# Teensy.net
KiCad netlist of a schematic drawn in Altium Designer
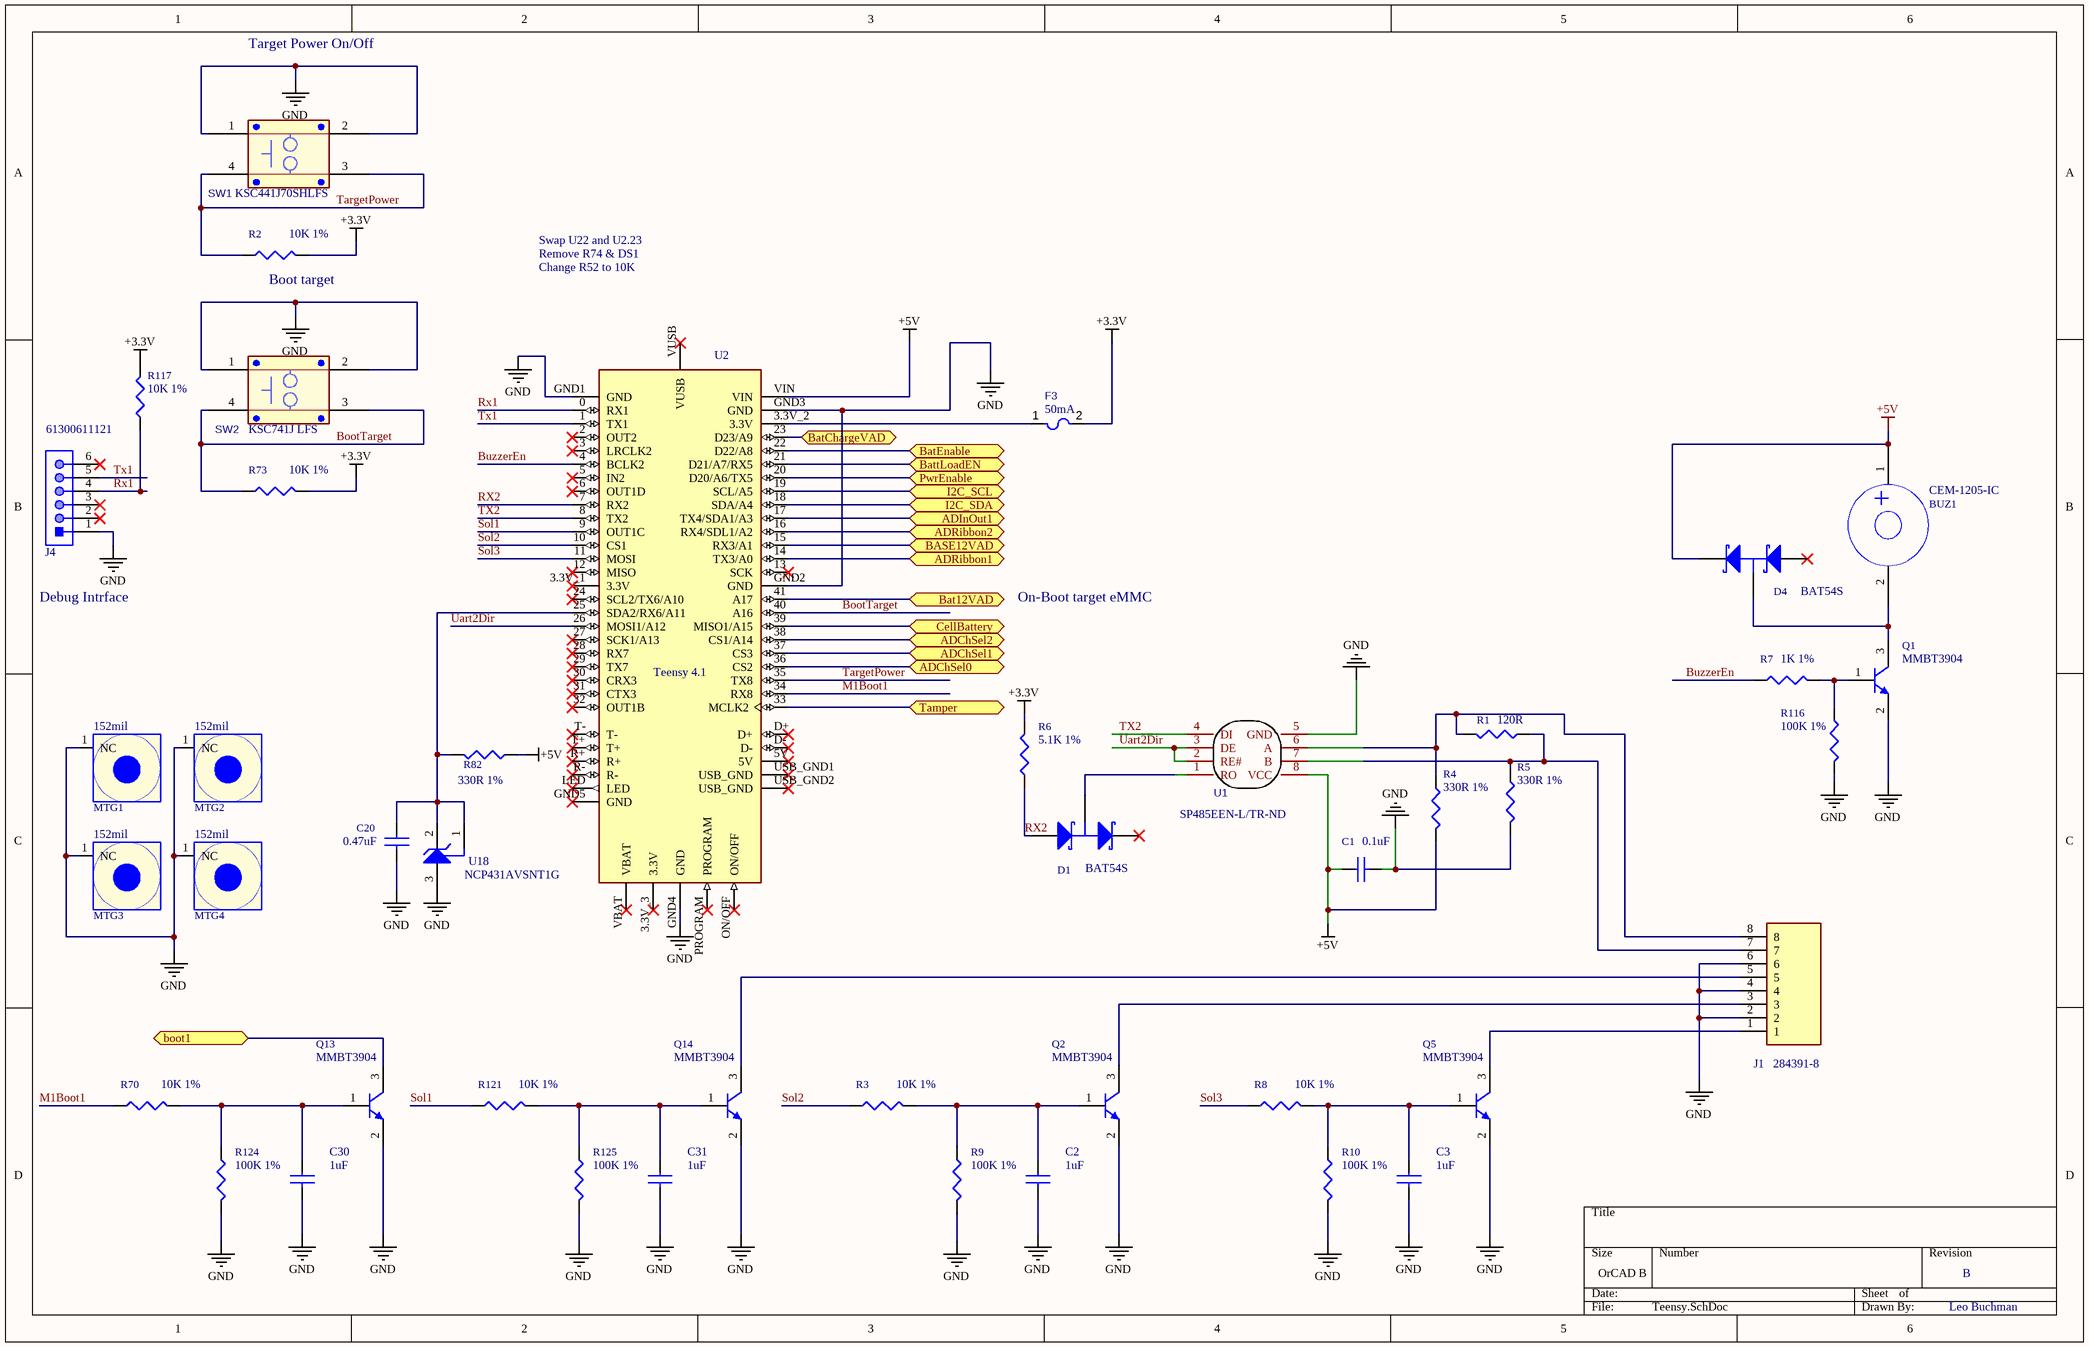
[diagram p0: Teensy.SchDoc]

(export (version "E")
  (design (tool "Eeschema 10.0.6"))
  (components
    (comp (ref "BUZ1")
      (value "CEM-1205-IC")
      (footprint "BUZZ-MB5120C")
      (description "12 mm, 5 Vdc, 92 dB, Through Hole, Driving Circuit, Magnetic Audio Indicator Buzzer")
      (fields (field (name "ADI PART NUMBER") "3716-0001") (field (name "VOLTAGE") "5V"))
      (libsource (lib "Leo-Home-SQL-Lib") (part "S2-BZ-0001"))
    )
    (comp (ref "C1")
      (value "0.1uF")
      (footprint "C0402")
      (description "Cap Ceramic 0.1uF 50V X7R 10% Pad SMD 0402 125C Automotive T/R")
      (fields
        (field (name "MANUFACTURER") "Murata")
        (field (name "MANUFACTURER PART NUMBER") "GRT155R71H104KE01D")
      )
      (libsource (lib "Leo-Home-SQL-Lib") (part "CAPNP"))
    )
    (comp (ref "C2")
      (value "1uF")
      (footprint "C0402")
      (description "CAP CER 1UF 10V Y5V 0402")
      (fields
        (field (name "MANUFACTURER") "KEMET")
        (field (name "MANUFACTURER PART NUMBER") "C0402C105Z8VAC7867")
      )
      (libsource (lib "Leo-Home-SQL-Lib") (part "CAPNP"))
    )
    (comp (ref "C3")
      (value "1uF")
      (footprint "C0402")
      (description "CAP CER 1UF 10V Y5V 0402")
      (fields
        (field (name "MANUFACTURER") "KEMET")
        (field (name "MANUFACTURER PART NUMBER") "C0402C105Z8VAC7867")
      )
      (libsource (lib "Leo-Home-SQL-Lib") (part "CAPNP"))
    )
    (comp (ref "C20")
      (value "0.47uF")
      (footprint "C0402")
      (description "CAP CER 0.47UF 16V Y5V 0402")
      (fields
        (field (name "MANUFACTURER") "Yageo")
        (field (name "MANUFACTURER PART NUMBER") "CC0402ZRY5V7BB474")
      )
      (libsource (lib "Leo-Home-SQL-Lib") (part "CAPNP"))
    )
    (comp (ref "C30")
      (value "1uF")
      (footprint "C0402")
      (description "CAP CER 1UF 10V Y5V 0402")
      (fields
        (field (name "MANUFACTURER") "KEMET")
        (field (name "MANUFACTURER PART NUMBER") "C0402C105Z8VAC7867")
      )
      (libsource (lib "Leo-Home-SQL-Lib") (part "CAPNP"))
    )
    (comp (ref "C31")
      (value "1uF")
      (footprint "C0402")
      (description "CAP CER 1UF 10V Y5V 0402")
      (fields
        (field (name "MANUFACTURER") "KEMET")
        (field (name "MANUFACTURER PART NUMBER") "C0402C105Z8VAC7867")
      )
      (libsource (lib "Leo-Home-SQL-Lib") (part "CAPNP"))
    )
    (comp (ref "D1")
      (value "BAT54S")
      (footprint "sot23-3")
      (description "DIODE SCHOTTKY 30V 150MA SOT23-3")
      (fields
        (field (name "MANUFACTURER") "Sangdest Microelectronics")
        (field (name "MANUFACTURER_1") "ON Semiconductor / Fairchild")
      )
      (libsource (lib "Leo-Home-SQL-Lib") (part "BAT54S-7-F"))
    )
    (comp (ref "D4")
      (value "BAT54S")
      (footprint "sot23-3")
      (description "DIODE SCHOTTKY 30V 150MA SOT23-3")
      (fields
        (field (name "MANUFACTURER") "Sangdest Microelectronics")
        (field (name "MANUFACTURER_1") "ON Semiconductor / Fairchild")
      )
      (libsource (lib "Leo-Home-SQL-Lib") (part "BAT54S-7-F"))
    )
    (comp (ref "F3")
      (value "50mA")
      (footprint "F0603")
      (description "Ptc Reset Fuse 15V 50MA 0603")
      (fields (field (name "MANUFACTURER") "Littelfuse") (field (name "MANUFACTURER_1") "Bourns"))
      (libsource (lib "Leo-Home-SQL-Lib") (part "FusePTC"))
    )
    (comp (ref "J1")
      (value "284391-8")
      (footprint "TE_284391-8")
      (description "Conn Terminal Block F 8 POS 3.5mm Solder ST T")
      (fields (field (name "MF") "TE Connectivity") (field (name "DIGI-KEY_PART_NUMBER") "A98163-ND"))
      (libsource (lib "Leo-Home-SQL-Lib") (part "284391-8"))
    )
    (comp (ref "J4")
      (value "61300611121")
      (footprint "61300611121")
      (description "CONN HEADER 6 POS 2.54")
      (fields (field (name "MANUFACTURER") "Wurth Electronics") (field (name "LCSC PART NUMBER") "C2833331"))
      (libsource (lib "Leo-Home-SQL-Lib") (part "CMP-1502-01070-1"))
    )
    (comp (ref "MTG1")
      (value "152mil")
      (footprint "MNT-HOLE-169-350")
      (description "Plated")
      (libsource (lib "Leo-Home-SQL-Lib") (part "HoleSym-001"))
    )
    (comp (ref "MTG2")
      (value "152mil")
      (footprint "MNT-HOLE-169-350")
      (description "Plated")
      (libsource (lib "Leo-Home-SQL-Lib") (part "HoleSym-001"))
    )
    (comp (ref "MTG3")
      (value "152mil")
      (footprint "MNT-HOLE-169-350")
      (description "Plated")
      (libsource (lib "Leo-Home-SQL-Lib") (part "HoleSym-001"))
    )
    (comp (ref "MTG4")
      (value "152mil")
      (footprint "MNT-HOLE-169-350")
      (description "Plated")
      (libsource (lib "Leo-Home-SQL-Lib") (part "HoleSym-001"))
    )
    (comp (ref "Q1")
      (value "MMBT3904")
      (footprint "sot23-3")
      (description "Trans GP BJT NPN 60V 0.2A 350mW Automotive 3-Pin SOT-23 T/R")
      (fields (field (name "MANUFACTURER") "ON Semiconductor / Fairchild") (field (name "POWER") "225mW"))
      (libsource (lib "Leo-Home-SQL-Lib") (part "BJT-NPN"))
    )
    (comp (ref "Q2")
      (value "MMBT3904")
      (footprint "sot23-3")
      (description "Trans GP BJT NPN 60V 0.2A 350mW Automotive 3-Pin SOT-23 T/R")
      (fields (field (name "MANUFACTURER") "ON Semiconductor / Fairchild") (field (name "POWER") "225mW"))
      (libsource (lib "Leo-Home-SQL-Lib") (part "BJT-NPN"))
    )
    (comp (ref "Q5")
      (value "MMBT3904")
      (footprint "sot23-3")
      (description "Trans GP BJT NPN 60V 0.2A 350mW Automotive 3-Pin SOT-23 T/R")
      (fields (field (name "MANUFACTURER") "ON Semiconductor / Fairchild") (field (name "POWER") "225mW"))
      (libsource (lib "Leo-Home-SQL-Lib") (part "BJT-NPN"))
    )
    (comp (ref "Q13")
      (value "MMBT3904")
      (footprint "sot23-3")
      (description "Trans GP BJT NPN 60V 0.2A 350mW Automotive 3-Pin SOT-23 T/R")
      (fields (field (name "MANUFACTURER") "ON Semiconductor / Fairchild") (field (name "POWER") "225mW"))
      (libsource (lib "Leo-Home-SQL-Lib") (part "BJT-NPN"))
    )
    (comp (ref "Q14")
      (value "MMBT3904")
      (footprint "sot23-3")
      (description "Trans GP BJT NPN 60V 0.2A 350mW Automotive 3-Pin SOT-23 T/R")
      (fields (field (name "MANUFACTURER") "ON Semiconductor / Fairchild") (field (name "POWER") "225mW"))
      (libsource (lib "Leo-Home-SQL-Lib") (part "BJT-NPN"))
    )
    (comp (ref "R1")
      (value "120R")
      (footprint "R0402")
      (description "Res Thick Film 0402 120 Ohm 1% 0.063W(1/16W) ±100ppm/C Pad SMD Automotive T/R")
      (fields
        (field (name "MANUFACTURER") "Stackpole Electronics")
        (field (name "MANUFACTURER PART NUMBER") "RMCF0402FT120R")
      )
      (libsource (lib "Leo-Home-SQL-Lib") (part "Resistor"))
    )
    (comp (ref "R2")
      (value "10K 1%")
      (footprint "R0402")
      (description "Thick Film 0402 10K OHM 1% 1/16W 0402")
      (fields
        (field (name "MANUFACTURER") "Yageo")
        (field (name "MANUFACTURER PART NUMBER") "RC0402FR-0710KP")
      )
      (libsource (lib "Leo-Home-SQL-Lib") (part "Resistor"))
    )
    (comp (ref "R3")
      (value "10K 1%")
      (footprint "R0402")
      (description "Thick Film 0402 10K OHM 1% 1/16W 0402")
      (fields
        (field (name "MANUFACTURER") "Yageo")
        (field (name "MANUFACTURER PART NUMBER") "RC0402FR-0710KP")
      )
      (libsource (lib "Leo-Home-SQL-Lib") (part "Resistor"))
    )
    (comp (ref "R4")
      (value "330R 1%")
      (footprint "R0402")
      (description "Thick Film 0402 330 Ohm 1% 1/16W ±100ppm/°C Molded SMD Paper T/R")
      (fields
        (field (name "MANUFACTURER") "Yageo")
        (field (name "MANUFACTURER PART NUMBER") "AF0402FR-07330RL")
      )
      (libsource (lib "Leo-Home-SQL-Lib") (part "Resistor"))
    )
    (comp (ref "R5")
      (value "330R 1%")
      (footprint "R0402")
      (description "Thick Film 0402 330 Ohm 1% 1/16W ±100ppm/°C Molded SMD Paper T/R")
      (fields
        (field (name "MANUFACTURER") "Yageo")
        (field (name "MANUFACTURER PART NUMBER") "AF0402FR-07330RL")
      )
      (libsource (lib "Leo-Home-SQL-Lib") (part "Resistor"))
    )
    (comp (ref "R6")
      (value "5.1K 1%")
      (footprint "R0402")
      (description "Thick Film 0402 5.1K Ohm 1% 1/16W 0402")
      (fields
        (field (name "MANUFACTURER") "Stackpole Electronics")
        (field (name "MANUFACTURER PART NUMBER") "RMCF0402FT5K10")
      )
      (libsource (lib "Leo-Home-SQL-Lib") (part "Resistor"))
    )
    (comp (ref "R7")
      (value "1K 1%")
      (footprint "R0402")
      (description "Thick Film 0402 1K Ohm 1% 1/8W 0402")
      (fields
        (field (name "MANUFACTURER") "TE Connectivity")
        (field (name "MANUFACTURER PART NUMBER") "CRGP0402F1K0")
      )
      (libsource (lib "Leo-Home-SQL-Lib") (part "Resistor"))
    )
    (comp (ref "R8")
      (value "10K 1%")
      (footprint "R0402")
      (description "Thick Film 0402 10K OHM 1% 1/16W 0402")
      (fields
        (field (name "MANUFACTURER") "Yageo")
        (field (name "MANUFACTURER PART NUMBER") "RC0402FR-0710KP")
      )
      (libsource (lib "Leo-Home-SQL-Lib") (part "Resistor"))
    )
    (comp (ref "R9")
      (value "100K 1%")
      (footprint "R0402")
      (description "Thick Film 0402 100K OHM 1% 1/16W 0402")
      (fields
        (field (name "MANUFACTURER") "Stackpole Electronics")
        (field (name "MANUFACTURER PART NUMBER") "RMCF0402FT100K")
      )
      (libsource (lib "Leo-Home-SQL-Lib") (part "Resistor"))
    )
    (comp (ref "R10")
      (value "100K 1%")
      (footprint "R0402")
      (description "Thick Film 0402 100K OHM 1% 1/16W 0402")
      (fields
        (field (name "MANUFACTURER") "Stackpole Electronics")
        (field (name "MANUFACTURER PART NUMBER") "RMCF0402FT100K")
      )
      (libsource (lib "Leo-Home-SQL-Lib") (part "Resistor"))
    )
    (comp (ref "R70")
      (value "10K 1%")
      (footprint "R0402")
      (description "Thick Film 0402 10K OHM 1% 1/16W 0402")
      (fields
        (field (name "MANUFACTURER") "Yageo")
        (field (name "MANUFACTURER PART NUMBER") "RC0402FR-0710KP")
      )
      (libsource (lib "Leo-Home-SQL-Lib") (part "Resistor"))
    )
    (comp (ref "R73")
      (value "10K 1%")
      (footprint "R0402")
      (description "Thick Film 0402 10K OHM 1% 1/16W 0402")
      (fields
        (field (name "MANUFACTURER") "Yageo")
        (field (name "MANUFACTURER PART NUMBER") "RC0402FR-0710KP")
      )
      (libsource (lib "Leo-Home-SQL-Lib") (part "Resistor"))
    )
    (comp (ref "R82")
      (value "330R 1%")
      (footprint "R0402")
      (description "Thick Film 0402 330 Ohm 1% 1/16W ±100ppm/°C Molded SMD Paper T/R")
      (fields
        (field (name "MANUFACTURER") "Yageo")
        (field (name "MANUFACTURER PART NUMBER") "AF0402FR-07330RL")
      )
      (libsource (lib "Leo-Home-SQL-Lib") (part "Resistor"))
    )
    (comp (ref "R116")
      (value "100K 1%")
      (footprint "R0402")
      (description "Thick Film 0402 100K OHM 1% 1/16W 0402")
      (fields
        (field (name "MANUFACTURER") "Stackpole Electronics")
        (field (name "MANUFACTURER PART NUMBER") "RMCF0402FT100K")
      )
      (libsource (lib "Leo-Home-SQL-Lib") (part "Resistor"))
    )
    (comp (ref "R117")
      (value "10K 1%")
      (footprint "R0402")
      (description "Thick Film 0402 10K OHM 1% 1/16W 0402")
      (fields
        (field (name "MANUFACTURER") "Yageo")
        (field (name "MANUFACTURER PART NUMBER") "RC0402FR-0710KP")
      )
      (libsource (lib "Leo-Home-SQL-Lib") (part "Resistor"))
    )
    (comp (ref "R121")
      (value "10K 1%")
      (footprint "R0402")
      (description "Thick Film 0402 10K OHM 1% 1/16W 0402")
      (fields
        (field (name "MANUFACTURER") "Yageo")
        (field (name "MANUFACTURER PART NUMBER") "RC0402FR-0710KP")
      )
      (libsource (lib "Leo-Home-SQL-Lib") (part "Resistor"))
    )
    (comp (ref "R124")
      (value "100K 1%")
      (footprint "R0402")
      (description "Thick Film 0402 100K OHM 1% 1/16W 0402")
      (fields
        (field (name "MANUFACTURER") "Stackpole Electronics")
        (field (name "MANUFACTURER PART NUMBER") "RMCF0402FT100K")
      )
      (libsource (lib "Leo-Home-SQL-Lib") (part "Resistor"))
    )
    (comp (ref "R125")
      (value "100K 1%")
      (footprint "R0402")
      (description "Thick Film 0402 100K OHM 1% 1/16W 0402")
      (fields
        (field (name "MANUFACTURER") "Stackpole Electronics")
        (field (name "MANUFACTURER PART NUMBER") "RMCF0402FT100K")
      )
      (libsource (lib "Leo-Home-SQL-Lib") (part "Resistor"))
    )
    (comp (ref "SW1")
      (value "KSC441J70SHLFS")
      (footprint "SON4_KSC741JLFS_CNK-red")
      (description "Switch Tactile N.O. SPST Round Button J-Bend")
      (fields (field (name "LCSC PART NUMBER") "C221748") (field (name "MANUFACTURER") "ITT C&K"))
      (libsource (lib "Leo-Home-SQL-Lib") (part "SW_Tactile"))
    )
    (comp (ref "SW2")
      (value "KSC741J LFS")
      (footprint "SON4_KSC741JLFS_CNK-blue")
      (description "Switch Tactile N.O. SPST Round Button J-Bend")
      (fields (field (name "LCSC PART NUMBER") "C221766") (field (name "MANUFACTURER") "ITT C&K"))
      (libsource (lib "Leo-Home-SQL-Lib") (part "SW_Tactile"))
    )
    (comp (ref "U1")
      (value "SP485EEN-L/TR-ND")
      (footprint "NSOIC-8")
      (description "IC TXRX RS485 HALF DUPLEX 8SOIC")
      (fields
        (field (name "BOM_MANUFACTURER PART") "SP485EEN-L/TR")
        (field (name "BOM_SUPPLIER PART") "C6855")
      )
      (libsource (lib "Leo-Home-SQL-Lib") (part "SP485EEN-L/TR"))
    )
    (comp (ref "U2")
      (value "Teensy 4.1")
      (footprint "MODULE_DEV-16771 - headers")
      (description "Teensy 4.1 Development Board")
      (fields (field (name "MANUFACTURER") "SparkFun") (field (name "MANUFACTURER PART NUMBER") "DEV-16771"))
      (libsource (lib "Leo-Home-SQL-Lib") (part "DEV-16771"))
    )
    (comp (ref "U18")
      (value "NCP431AVSNT1G")
      (footprint "sot23-3")
      (description "V-Ref Adjustable 2.5V to 36V 100mA 3-Pin SOT-")
      (fields (field (name "MANUFACTURER") "ON Semiconductor") (field (name "PARTNUMBER") "TL431ACLP"))
      (libsource (lib "Leo-Home-SQL-Lib") (part "CMP-0366-00039-2"))
    )
  )
  (nets
    (net (code "1") (name "+3.3V") (class "Default")
      (node (ref "F3") (pin "2") (pinfunction "2_2") (pintype "passive"))
      (node (ref "R117") (pin "2") (pinfunction "2_2") (pintype "passive"))
      (node (ref "R2") (pin "2") (pinfunction "2_2") (pintype "passive"))
      (node (ref "R6") (pin "2") (pinfunction "2_2") (pintype "passive"))
      (node (ref "R73") (pin "2") (pinfunction "2_2") (pintype "passive"))
    )
    (net (code "2") (name "+5V") (class "Default")
      (node (ref "BUZ1") (pin "1") (pinfunction "POS_1") (pintype "power_in"))
      (node (ref "C1") (pin "1") (pinfunction "1_1") (pintype "passive"))
      (node (ref "D4") (pin "2") (pinfunction "K_2") (pintype "passive"))
      (node (ref "R4") (pin "2") (pinfunction "2_2") (pintype "passive"))
      (node (ref "R82") (pin "1") (pinfunction "1_1") (pintype "passive"))
      (node (ref "U1") (pin "8") (pinfunction "VCC_8") (pintype "passive"))
      (node (ref "U2") (pin "VIN") (pinfunction "VIN_VIN") (pintype "power_in"))
    )
    (net (code "3") (name "/ADChSel0") (class "Default")
      (node (ref "U2") (pin "36") (pinfunction "CS2_36") (pintype "bidirectional"))
    )
    (net (code "4") (name "/ADChSel1") (class "Default")
      (node (ref "U2") (pin "37") (pinfunction "CS3_37") (pintype "bidirectional"))
    )
    (net (code "5") (name "/ADChSel2") (class "Default")
      (node (ref "U2") (pin "38") (pinfunction "CS1/A14_38") (pintype "bidirectional"))
    )
    (net (code "6") (name "/ADInOut1") (class "Default")
      (node (ref "U2") (pin "17") (pinfunction "TX4/SDA1/A3_17") (pintype "bidirectional"))
    )
    (net (code "7") (name "/ADRibbon1") (class "Default")
      (node (ref "U2") (pin "14") (pinfunction "TX3/A0_14") (pintype "bidirectional"))
    )
    (net (code "8") (name "/ADRibbon2") (class "Default")
      (node (ref "U2") (pin "16") (pinfunction "RX4/SDL1/A2_16") (pintype "bidirectional"))
    )
    (net (code "9") (name "/BASE12VAD") (class "Default")
      (node (ref "U2") (pin "15") (pinfunction "RX3/A1_15") (pintype "bidirectional"))
    )
    (net (code "10") (name "/Bat12VAD") (class "Default")
      (node (ref "U2") (pin "41") (pinfunction "A17_41") (pintype "bidirectional"))
    )
    (net (code "11") (name "/BatChargeVAD") (class "Default")
      (node (ref "U2") (pin "23") (pinfunction "D23/A9_23") (pintype "bidirectional"))
    )
    (net (code "12") (name "/BatEnable") (class "Default")
      (node (ref "U2") (pin "22") (pinfunction "D22/A8_22") (pintype "bidirectional"))
    )
    (net (code "13") (name "/BattLoadEN") (class "Default")
      (node (ref "U2") (pin "21") (pinfunction "D21/A7/RX5_21") (pintype "bidirectional"))
    )
    (net (code "14") (name "/BootTarget") (class "Default")
      (node (ref "R73") (pin "1") (pinfunction "1_1") (pintype "passive"))
      (node (ref "SW2") (pin "3") (pinfunction "3_3") (pintype "passive"))
      (node (ref "SW2") (pin "4") (pinfunction "4_4") (pintype "passive"))
      (node (ref "U2") (pin "40") (pinfunction "A16_40") (pintype "bidirectional"))
    )
    (net (code "15") (name "/BuzzerEn") (class "Default")
      (node (ref "R7") (pin "1") (pinfunction "1_1") (pintype "passive"))
      (node (ref "U2") (pin "4") (pinfunction "BCLK2_4") (pintype "bidirectional"))
    )
    (net (code "16") (name "/CellBattery") (class "Default")
      (node (ref "U2") (pin "39") (pinfunction "MISO1/A15_39") (pintype "bidirectional"))
    )
    (net (code "17") (name "/I2C_SCL") (class "Default")
      (node (ref "U2") (pin "19") (pinfunction "SCL/A5_19") (pintype "bidirectional"))
    )
    (net (code "18") (name "/I2C_SDA") (class "Default")
      (node (ref "U2") (pin "18") (pinfunction "SDA/A4_18") (pintype "bidirectional"))
    )
    (net (code "19") (name "/M1Boot1") (class "Default")
      (node (ref "R70") (pin "1") (pinfunction "1_1") (pintype "passive"))
      (node (ref "U2") (pin "34") (pinfunction "RX8_34") (pintype "bidirectional"))
    )
    (net (code "20") (name "/PwrEnable") (class "Default")
      (node (ref "U2") (pin "20") (pinfunction "D20/A6/TX5_20") (pintype "bidirectional"))
    )
    (net (code "21") (name "/RX2") (class "Default")
      (node (ref "D1") (pin "1") (pinfunction "A_1") (pintype "passive"))
      (node (ref "R6") (pin "1") (pinfunction "1_1") (pintype "passive"))
      (node (ref "U2") (pin "7") (pinfunction "RX2_7") (pintype "bidirectional"))
    )
    (net (code "22") (name "/Rx1") (class "Default")
      (node (ref "J4") (pin "4") (pinfunction "4_4") (pintype "passive"))
      (node (ref "R117") (pin "1") (pinfunction "1_1") (pintype "passive"))
      (node (ref "U2") (pin "0") (pinfunction "RX1_0") (pintype "bidirectional"))
    )
    (net (code "23") (name "/Sol1") (class "Default")
      (node (ref "R121") (pin "1") (pinfunction "1_1") (pintype "passive"))
      (node (ref "U2") (pin "9") (pinfunction "OUT1C_9") (pintype "bidirectional"))
    )
    (net (code "24") (name "/Sol2") (class "Default")
      (node (ref "R3") (pin "1") (pinfunction "1_1") (pintype "passive"))
      (node (ref "U2") (pin "10") (pinfunction "CS1_10") (pintype "bidirectional"))
    )
    (net (code "25") (name "/Sol3") (class "Default")
      (node (ref "R8") (pin "1") (pinfunction "1_1") (pintype "passive"))
      (node (ref "U2") (pin "11") (pinfunction "MOSI_11") (pintype "bidirectional"))
    )
    (net (code "26") (name "/TX2") (class "Default")
      (node (ref "U1") (pin "4") (pinfunction "DI_4") (pintype "passive"))
      (node (ref "U2") (pin "8") (pinfunction "TX2_8") (pintype "bidirectional"))
    )
    (net (code "27") (name "/Tamper") (class "Default")
      (node (ref "U2") (pin "33") (pinfunction "MCLK2_33") (pintype "bidirectional"))
    )
    (net (code "28") (name "/TargetPower") (class "Default")
      (node (ref "R2") (pin "1") (pinfunction "1_1") (pintype "passive"))
      (node (ref "SW1") (pin "3") (pinfunction "3_3") (pintype "passive"))
      (node (ref "SW1") (pin "4") (pinfunction "4_4") (pintype "passive"))
      (node (ref "U2") (pin "35") (pinfunction "TX8_35") (pintype "bidirectional"))
    )
    (net (code "29") (name "/Tx1") (class "Default")
      (node (ref "J4") (pin "5") (pinfunction "5_5") (pintype "passive"))
      (node (ref "U2") (pin "1") (pinfunction "TX1_1") (pintype "bidirectional"))
    )
    (net (code "30") (name "/Uart2Dir") (class "Default")
      (node (ref "U1") (pin "2") (pinfunction "RE#_2") (pintype "passive"))
      (node (ref "U1") (pin "3") (pinfunction "DE_3") (pintype "passive"))
      (node (ref "U2") (pin "26") (pinfunction "MOSI1/A12_26") (pintype "bidirectional"))
    )
    (net (code "31") (name "/boot1") (class "Default")
      (node (ref "Q13") (pin "3") (pinfunction "C_3") (pintype "passive"))
    )
    (net (code "32") (name "GND") (class "Default")
      (node (ref "C1") (pin "2") (pinfunction "2_2") (pintype "passive"))
      (node (ref "C2") (pin "2") (pinfunction "2_2") (pintype "passive"))
      (node (ref "C20") (pin "2") (pinfunction "2_2") (pintype "passive"))
      (node (ref "C3") (pin "2") (pinfunction "2_2") (pintype "passive"))
      (node (ref "C30") (pin "2") (pinfunction "2_2") (pintype "passive"))
      (node (ref "C31") (pin "2") (pinfunction "2_2") (pintype "passive"))
      (node (ref "J1") (pin "2") (pinfunction "2_2") (pintype "passive"))
      (node (ref "J1") (pin "4") (pinfunction "4_4") (pintype "passive"))
      (node (ref "J1") (pin "6") (pinfunction "6_6") (pintype "passive"))
      (node (ref "J4") (pin "1") (pinfunction "1_1") (pintype "passive"))
      (node (ref "MTG1") (pin "1") (pinfunction "NC_1") (pintype "passive"))
      (node (ref "MTG2") (pin "1") (pinfunction "NC_1") (pintype "passive"))
      (node (ref "MTG3") (pin "1") (pinfunction "NC_1") (pintype "passive"))
      (node (ref "MTG4") (pin "1") (pinfunction "NC_1") (pintype "passive"))
      (node (ref "Q1") (pin "2") (pinfunction "E_2") (pintype "passive"))
      (node (ref "Q13") (pin "2") (pinfunction "E_2") (pintype "passive"))
      (node (ref "Q14") (pin "2") (pinfunction "E_2") (pintype "passive"))
      (node (ref "Q2") (pin "2") (pinfunction "E_2") (pintype "passive"))
      (node (ref "Q5") (pin "2") (pinfunction "E_2") (pintype "passive"))
      (node (ref "R10") (pin "2") (pinfunction "2_2") (pintype "passive"))
      (node (ref "R116") (pin "2") (pinfunction "2_2") (pintype "passive"))
      (node (ref "R124") (pin "2") (pinfunction "2_2") (pintype "passive"))
      (node (ref "R125") (pin "2") (pinfunction "2_2") (pintype "passive"))
      (node (ref "R5") (pin "2") (pinfunction "2_2") (pintype "passive"))
      (node (ref "R9") (pin "2") (pinfunction "2_2") (pintype "passive"))
      (node (ref "SW1") (pin "1") (pinfunction "1_1") (pintype "passive"))
      (node (ref "SW1") (pin "2") (pinfunction "2_2") (pintype "passive"))
      (node (ref "SW2") (pin "1") (pinfunction "1_1") (pintype "passive"))
      (node (ref "SW2") (pin "2") (pinfunction "2_2") (pintype "passive"))
      (node (ref "U1") (pin "5") (pinfunction "GND_5") (pintype "passive"))
      (node (ref "U18") (pin "3") (pinfunction "ANODE_3") (pintype "passive"))
      (node (ref "U2") (pin "GND1") (pinfunction "GND_GND1") (pintype "power_in"))
      (node (ref "U2") (pin "GND2") (pinfunction "GND_GND2") (pintype "power_in"))
      (node (ref "U2") (pin "GND3") (pinfunction "GND_GND3") (pintype "power_in"))
      (node (ref "U2") (pin "GND4") (pinfunction "GND_GND4") (pintype "power_in"))
    )
    (net (code "33") (name "Net-(BUZ1-NEG)") (class "Default")
      (node (ref "BUZ1") (pin "2") (pinfunction "NEG_2") (pintype "power_in"))
      (node (ref "D4") (pin "3") (pinfunction "C_3") (pintype "passive"))
      (node (ref "Q1") (pin "3") (pinfunction "C_3") (pintype "passive"))
    )
    (net (code "34") (name "Net-(D1-C)") (class "Default")
      (node (ref "D1") (pin "3") (pinfunction "C_3") (pintype "passive"))
      (node (ref "U1") (pin "1") (pinfunction "RO_1") (pintype "passive"))
    )
    (net (code "35") (name "Net-(F3-Pad1)") (class "Default")
      (node (ref "F3") (pin "1") (pinfunction "1_1") (pintype "passive"))
      (node (ref "U2") (pin "3.3V_2") (pinfunction "3.3V_3.3V_2") (pintype "power_in"))
    )
    (net (code "36") (name "Net-(Q1-B)") (class "Default")
      (node (ref "Q1") (pin "1") (pinfunction "B_1") (pintype "passive"))
      (node (ref "R116") (pin "1") (pinfunction "1_1") (pintype "passive"))
      (node (ref "R7") (pin "2") (pinfunction "2_2") (pintype "passive"))
    )
    (net (code "37") (name "Net-(Q2-B)") (class "Default")
      (node (ref "C2") (pin "1") (pinfunction "1_1") (pintype "passive"))
      (node (ref "Q2") (pin "1") (pinfunction "B_1") (pintype "passive"))
      (node (ref "R3") (pin "2") (pinfunction "2_2") (pintype "passive"))
      (node (ref "R9") (pin "1") (pinfunction "1_1") (pintype "passive"))
    )
    (net (code "38") (name "Net-(Q2-C)") (class "Default")
      (node (ref "J1") (pin "3") (pinfunction "3_3") (pintype "passive"))
      (node (ref "Q2") (pin "3") (pinfunction "C_3") (pintype "passive"))
    )
    (net (code "39") (name "Net-(Q5-B)") (class "Default")
      (node (ref "C3") (pin "1") (pinfunction "1_1") (pintype "passive"))
      (node (ref "Q5") (pin "1") (pinfunction "B_1") (pintype "passive"))
      (node (ref "R10") (pin "1") (pinfunction "1_1") (pintype "passive"))
      (node (ref "R8") (pin "2") (pinfunction "2_2") (pintype "passive"))
    )
    (net (code "40") (name "Net-(Q5-C)") (class "Default")
      (node (ref "J1") (pin "1") (pinfunction "1_1") (pintype "passive"))
      (node (ref "Q5") (pin "3") (pinfunction "C_3") (pintype "passive"))
    )
    (net (code "41") (name "Net-(Q13-B)") (class "Default")
      (node (ref "C30") (pin "1") (pinfunction "1_1") (pintype "passive"))
      (node (ref "Q13") (pin "1") (pinfunction "B_1") (pintype "passive"))
      (node (ref "R124") (pin "1") (pinfunction "1_1") (pintype "passive"))
      (node (ref "R70") (pin "2") (pinfunction "2_2") (pintype "passive"))
    )
    (net (code "42") (name "Net-(Q14-B)") (class "Default")
      (node (ref "C31") (pin "1") (pinfunction "1_1") (pintype "passive"))
      (node (ref "Q14") (pin "1") (pinfunction "B_1") (pintype "passive"))
      (node (ref "R121") (pin "2") (pinfunction "2_2") (pintype "passive"))
      (node (ref "R125") (pin "1") (pinfunction "1_1") (pintype "passive"))
    )
    (net (code "43") (name "Net-(Q14-C)") (class "Default")
      (node (ref "J1") (pin "5") (pinfunction "5_5") (pintype "passive"))
      (node (ref "Q14") (pin "3") (pinfunction "C_3") (pintype "passive"))
    )
    (net (code "44") (name "Net-(U1-A)") (class "Default")
      (node (ref "J1") (pin "8") (pinfunction "8_8") (pintype "passive"))
      (node (ref "R1") (pin "2") (pinfunction "2_2") (pintype "passive"))
      (node (ref "R4") (pin "1") (pinfunction "1_1") (pintype "passive"))
      (node (ref "U1") (pin "6") (pinfunction "A_6") (pintype "passive"))
    )
    (net (code "45") (name "Net-(U1-B)") (class "Default")
      (node (ref "J1") (pin "7") (pinfunction "7_7") (pintype "passive"))
      (node (ref "R1") (pin "1") (pinfunction "1_1") (pintype "passive"))
      (node (ref "R5") (pin "1") (pinfunction "1_1") (pintype "passive"))
      (node (ref "U1") (pin "7") (pinfunction "B_7") (pintype "passive"))
    )
    (net (code "46") (name "Net-(U18-CATHODE)") (class "Default")
      (node (ref "C20") (pin "1") (pinfunction "1_1") (pintype "passive"))
      (node (ref "R82") (pin "2") (pinfunction "2_2") (pintype "passive"))
      (node (ref "U18") (pin "1") (pinfunction "REF_1") (pintype "passive"))
      (node (ref "U18") (pin "2") (pinfunction "CATHODE_2") (pintype "passive"))
      (node (ref "U2") (pin "25") (pinfunction "SDA2/RX6/A11_25") (pintype "bidirectional"))
    )
    (net (code "47") (name "unconnected-(D1-K-Pad2)") (class "Default")
      (node (ref "D1") (pin "2") (pinfunction "K_2") (pintype "passive+no_connect"))
    )
    (net (code "48") (name "unconnected-(D4-A-Pad1)") (class "Default")
      (node (ref "D4") (pin "1") (pinfunction "A_1") (pintype "passive+no_connect"))
    )
    (net (code "49") (name "unconnected-(J4-Pad2)") (class "Default")
      (node (ref "J4") (pin "2") (pinfunction "2_2") (pintype "passive+no_connect"))
    )
    (net (code "50") (name "unconnected-(J4-Pad3)") (class "Default")
      (node (ref "J4") (pin "3") (pinfunction "3_3") (pintype "passive+no_connect"))
    )
    (net (code "51") (name "unconnected-(J4-Pad6)") (class "Default")
      (node (ref "J4") (pin "6") (pinfunction "6_6") (pintype "passive+no_connect"))
    )
    (net (code "52") (name "unconnected-(U2-3.3V-Pad3.3V_1)") (class "Default")
      (node (ref "U2") (pin "3.3V_1") (pinfunction "3.3V_3.3V_1") (pintype "power_in+no_connect"))
    )
    (net (code "53") (name "unconnected-(U2-3.3V-Pad3.3V_3)") (class "Default")
      (node (ref "U2") (pin "3.3V_3") (pinfunction "3.3V_3.3V_3") (pintype "power_in+no_connect"))
    )
    (net (code "54") (name "unconnected-(U2-CRX3-Pad30)") (class "Default")
      (node (ref "U2") (pin "30") (pinfunction "CRX3_30") (pintype "bidirectional+no_connect"))
    )
    (net (code "55") (name "unconnected-(U2-CTX3-Pad31)") (class "Default")
      (node (ref "U2") (pin "31") (pinfunction "CTX3_31") (pintype "bidirectional+no_connect"))
    )
    (net (code "56") (name "unconnected-(U2-GND-PadGND5)") (class "Default")
      (node (ref "U2") (pin "GND5") (pinfunction "GND_GND5") (pintype "power_in+no_connect"))
    )
    (net (code "57") (name "unconnected-(U2-IN2-Pad5)") (class "Default")
      (node (ref "U2") (pin "5") (pinfunction "IN2_5") (pintype "bidirectional+no_connect"))
    )
    (net (code "58") (name "unconnected-(U2-LRCLK2-Pad3)") (class "Default")
      (node (ref "U2") (pin "3") (pinfunction "LRCLK2_3") (pintype "bidirectional+no_connect"))
    )
    (net (code "59") (name "unconnected-(U2-MISO-Pad12)") (class "Default")
      (node (ref "U2") (pin "12") (pinfunction "MISO_12") (pintype "bidirectional+no_connect"))
    )
    (net (code "60") (name "unconnected-(U2-OUT1B-Pad32)") (class "Default")
      (node (ref "U2") (pin "32") (pinfunction "OUT1B_32") (pintype "bidirectional+no_connect"))
    )
    (net (code "61") (name "unconnected-(U2-OUT1D-Pad6)") (class "Default")
      (node (ref "U2") (pin "6") (pinfunction "OUT1D_6") (pintype "bidirectional+no_connect"))
    )
    (net (code "62") (name "unconnected-(U2-OUT2-Pad2)") (class "Default")
      (node (ref "U2") (pin "2") (pinfunction "OUT2_2") (pintype "bidirectional+no_connect"))
    )
    (net (code "63") (name "unconnected-(U2-Pad5V)") (class "Default")
      (node (ref "U2") (pin "5V") (pinfunction "5V_5V") (pintype "power_in+no_connect"))
    )
    (net (code "64") (name "unconnected-(U2-PadD+)") (class "Default")
      (node (ref "U2") (pin "D+") (pinfunction "D+_D+") (pintype "bidirectional+no_connect"))
    )
    (net (code "65") (name "unconnected-(U2-PadD-)") (class "Default")
      (node (ref "U2") (pin "D-") (pinfunction "D-_D-") (pintype "bidirectional+no_connect"))
    )
    (net (code "66") (name "unconnected-(U2-PadLED)") (class "Default")
      (node (ref "U2") (pin "LED") (pinfunction "LED_LED") (pintype "output+no_connect"))
    )
    (net (code "67") (name "unconnected-(U2-PadON{slash}OFF)") (class "Default")
      (node (ref "U2") (pin "ON/OFF") (pinfunction "ON/OFF_ON/OFF") (pintype "input+no_connect"))
    )
    (net (code "68") (name "unconnected-(U2-PadPROGRAM)") (class "Default")
      (node (ref "U2") (pin "PROGRAM") (pinfunction "PROGRAM_PROGRAM") (pintype "input+no_connect"))
    )
    (net (code "69") (name "unconnected-(U2-PadR+)") (class "Default")
      (node (ref "U2") (pin "R+") (pinfunction "R+_R+") (pintype "bidirectional+no_connect"))
    )
    (net (code "70") (name "unconnected-(U2-PadR-)") (class "Default")
      (node (ref "U2") (pin "R-") (pinfunction "R-_R-") (pintype "bidirectional+no_connect"))
    )
    (net (code "71") (name "unconnected-(U2-PadT+)") (class "Default")
      (node (ref "U2") (pin "T+") (pinfunction "T+_T+") (pintype "bidirectional+no_connect"))
    )
    (net (code "72") (name "unconnected-(U2-PadT-)") (class "Default")
      (node (ref "U2") (pin "T-") (pinfunction "T-_T-") (pintype "bidirectional+no_connect"))
    )
    (net (code "73") (name "unconnected-(U2-PadVBAT)") (class "Default")
      (node (ref "U2") (pin "VBAT") (pinfunction "VBAT_VBAT") (pintype "passive+no_connect"))
    )
    (net (code "74") (name "unconnected-(U2-PadVUSB)") (class "Default")
      (node (ref "U2") (pin "VUSB") (pinfunction "VUSB_VUSB") (pintype "passive+no_connect"))
    )
    (net (code "75") (name "unconnected-(U2-RX7-Pad28)") (class "Default")
      (node (ref "U2") (pin "28") (pinfunction "RX7_28") (pintype "bidirectional+no_connect"))
    )
    (net (code "76") (name "unconnected-(U2-SCK-Pad13)") (class "Default")
      (node (ref "U2") (pin "13") (pinfunction "SCK_13") (pintype "bidirectional+no_connect"))
    )
    (net (code "77") (name "unconnected-(U2-SCK1{slash}A13-Pad27)") (class "Default")
      (node (ref "U2") (pin "27") (pinfunction "SCK1/A13_27") (pintype "bidirectional+no_connect"))
    )
    (net (code "78") (name "unconnected-(U2-SCL2{slash}TX6{slash}A10-Pad24)") (class "Default")
      (node (ref "U2") (pin "24") (pinfunction "SCL2/TX6/A10_24") (pintype "bidirectional+no_connect"))
    )
    (net (code "79") (name "unconnected-(U2-TX7-Pad29)") (class "Default")
      (node (ref "U2") (pin "29") (pinfunction "TX7_29") (pintype "bidirectional+no_connect"))
    )
    (net (code "80") (name "unconnected-(U2-USB_GND-PadUSB_GND1)") (class "Default")
      (node (ref "U2") (pin "USB_GND1") (pinfunction "USB_GND_USB_GND1") (pintype "power_in+no_connect"))
    )
    (net (code "81") (name "unconnected-(U2-USB_GND-PadUSB_GND2)") (class "Default")
      (node (ref "U2") (pin "USB_GND2") (pinfunction "USB_GND_USB_GND2") (pintype "power_in+no_connect"))
    )
  )
)
